# SCH_DMTBlinky_2025-11-07.net
KiCad netlist of a schematic drawn in EasyEDA
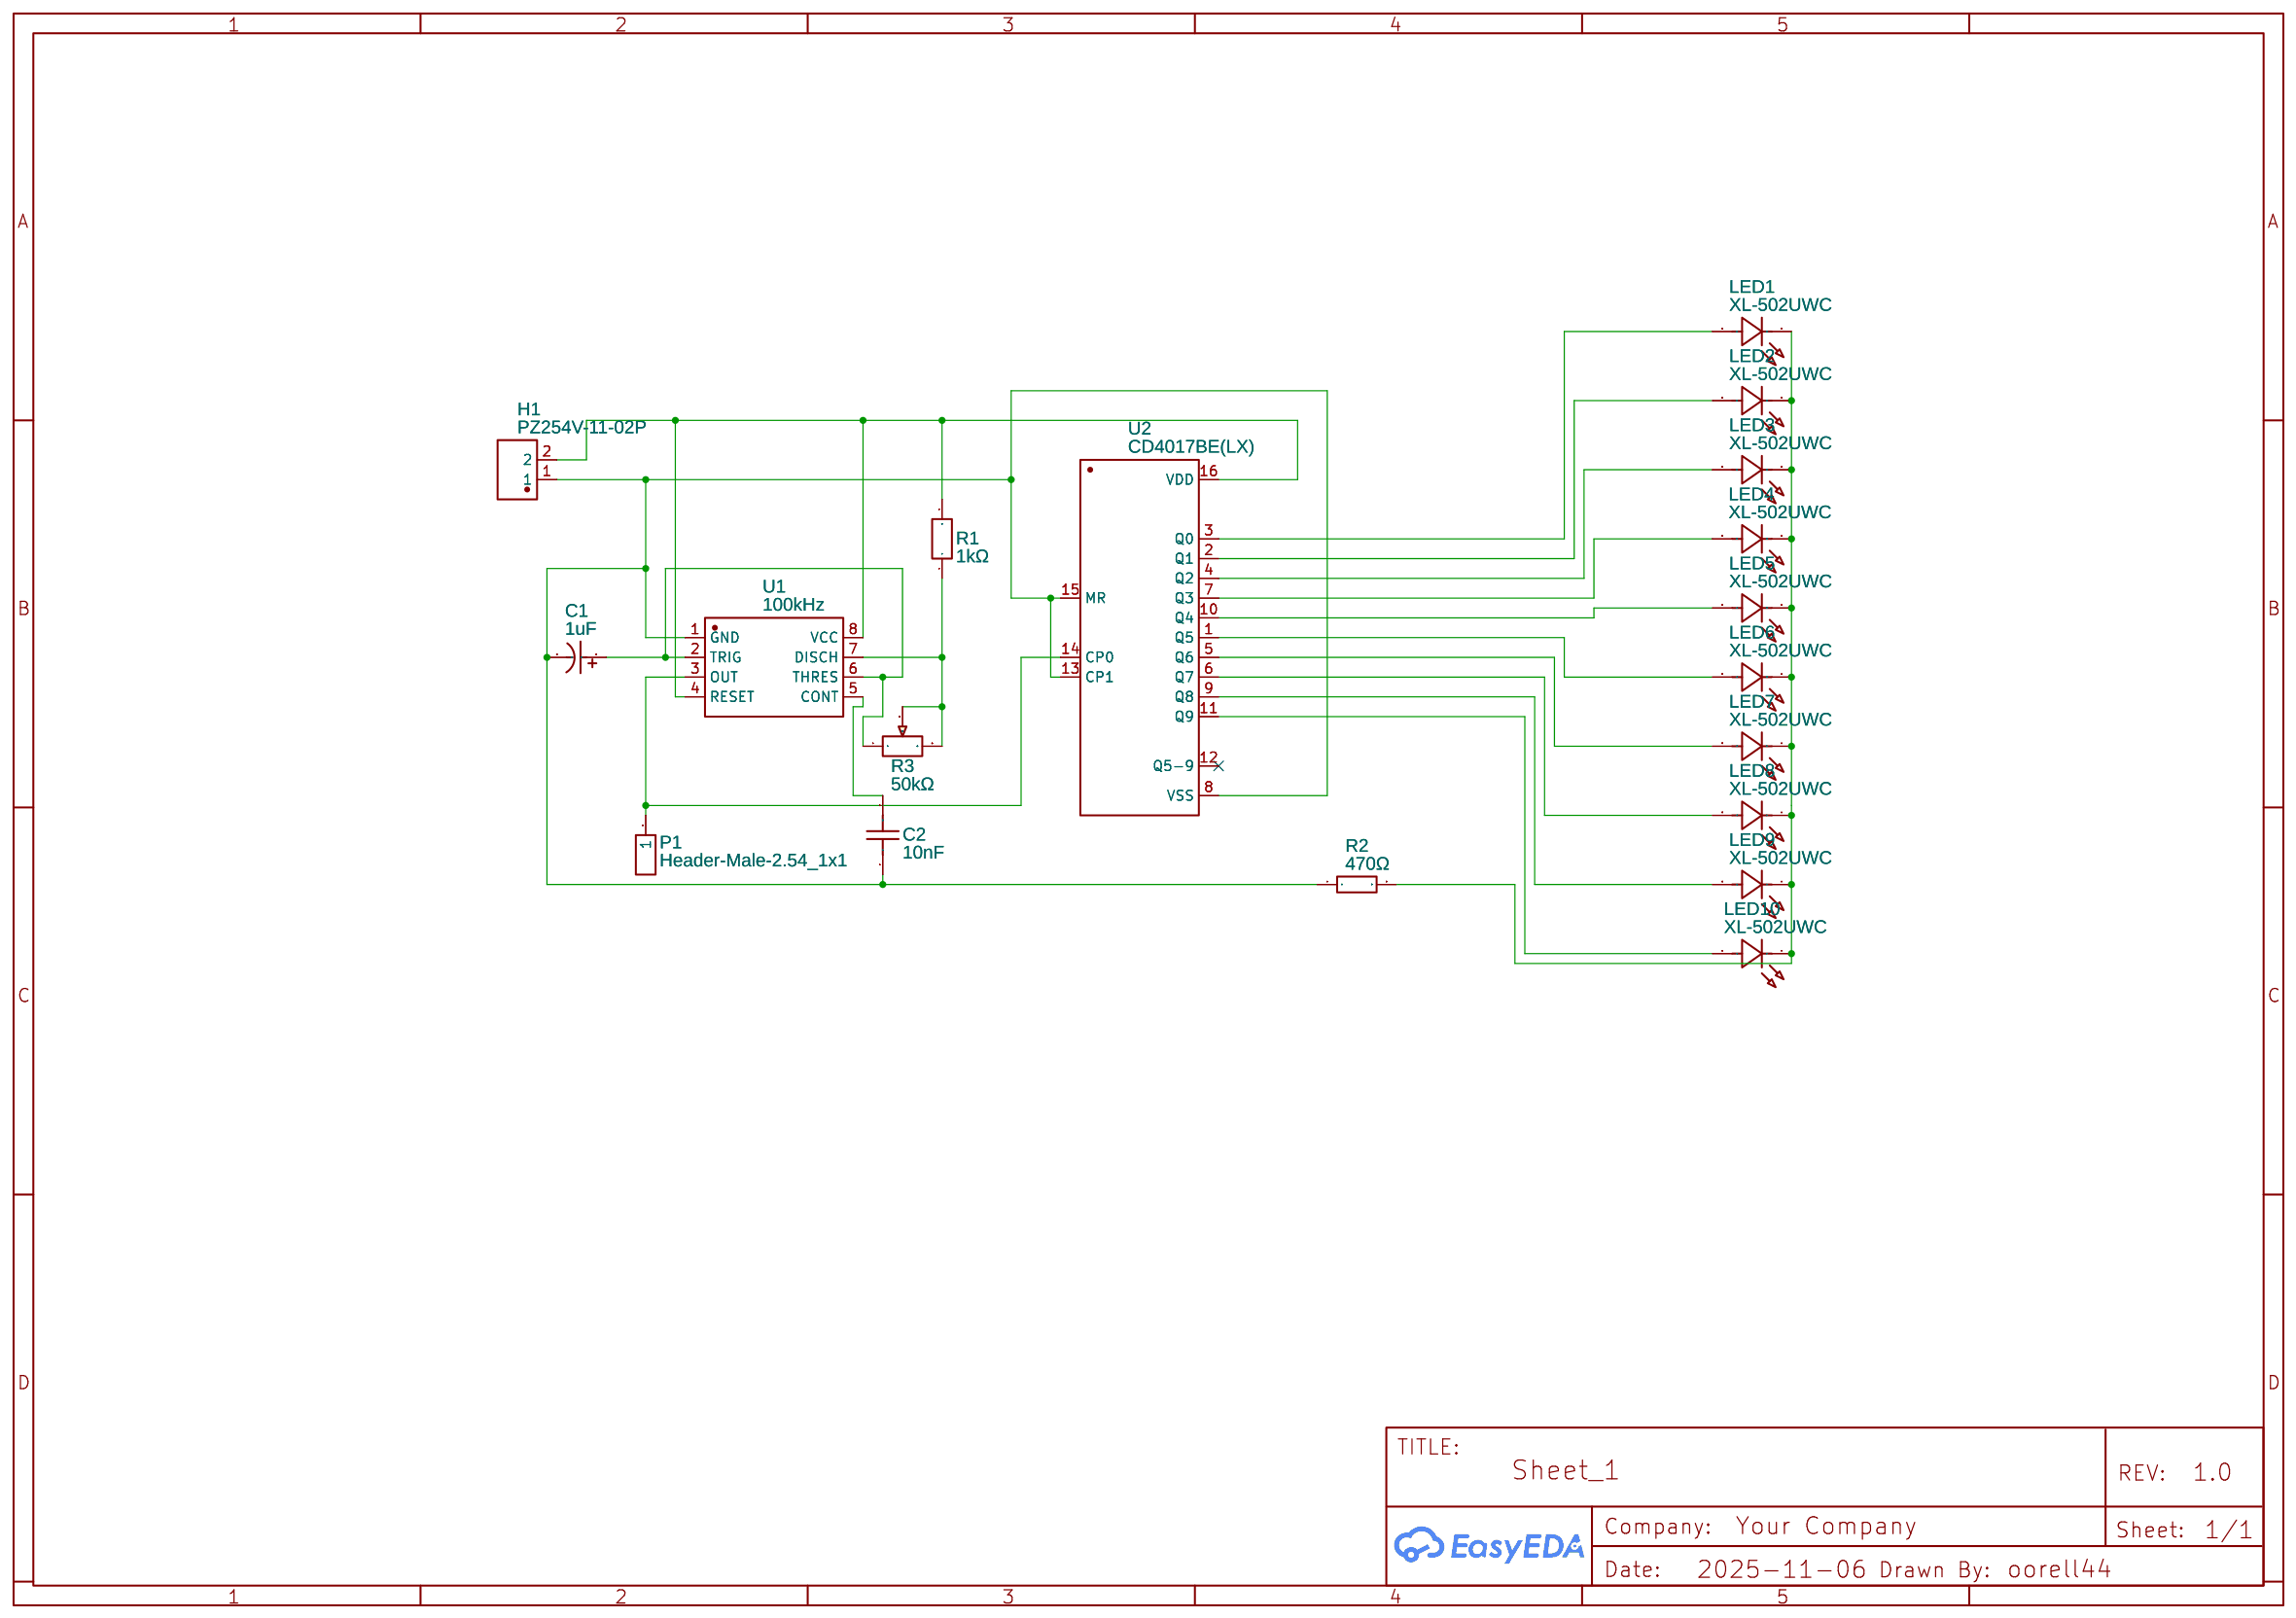
[diagram p0: schematic sheet]

(export (version "E")
  (design (tool "Eeschema 10.0.6"))
  (components
    (comp (ref "C1")
      (value "1uF")
      (fields (field (name "Manufacturer Part") "KF010M050C110A") (field (name "Manufacturer") "CapXon(丰宾)"))
      (libsource (lib "") (part "KF010M050C110A"))
    )
    (comp (ref "C2")
      (value "10nF")
      (fields (field (name "Manufacturer Part") "N09F1B103MN0B0S0N0") (field (name "Manufacturer") "STE(松田)"))
      (libsource (lib "") (part "N09F1B103MN0B0S0N0"))
    )
    (comp (ref "H1")
      (value "PZ254V-11-02P")
      (fields (field (name "Manufacturer") "XFCN(兴飞)"))
      (libsource (lib "") (part "PZ254V-11-02P"))
    )
    (comp (ref "LED1")
      (value "XL-502UWC")
      (fields (field (name "Manufacturer") "XINGLIGHT(成兴光)"))
      (libsource (lib "") (part "XL-502UWC"))
    )
    (comp (ref "LED2")
      (value "XL-502UWC")
      (fields (field (name "Manufacturer") "XINGLIGHT(成兴光)"))
      (libsource (lib "") (part "XL-502UWC"))
    )
    (comp (ref "LED3")
      (value "XL-502UWC")
      (fields (field (name "Manufacturer") "XINGLIGHT(成兴光)"))
      (libsource (lib "") (part "XL-502UWC"))
    )
    (comp (ref "LED4")
      (value "XL-502UWC")
      (fields (field (name "Manufacturer") "XINGLIGHT(成兴光)"))
      (libsource (lib "") (part "XL-502UWC"))
    )
    (comp (ref "LED5")
      (value "XL-502UWC")
      (fields (field (name "Manufacturer") "XINGLIGHT(成兴光)"))
      (libsource (lib "") (part "XL-502UWC"))
    )
    (comp (ref "LED6")
      (value "XL-502UWC")
      (fields (field (name "Manufacturer") "XINGLIGHT(成兴光)"))
      (libsource (lib "") (part "XL-502UWC"))
    )
    (comp (ref "LED7")
      (value "XL-502UWC")
      (fields (field (name "Manufacturer") "XINGLIGHT(成兴光)"))
      (libsource (lib "") (part "XL-502UWC"))
    )
    (comp (ref "LED8")
      (value "XL-502UWC")
      (fields (field (name "Manufacturer") "XINGLIGHT(成兴光)"))
      (libsource (lib "") (part "XL-502UWC"))
    )
    (comp (ref "LED9")
      (value "XL-502UWC")
      (fields (field (name "Manufacturer") "XINGLIGHT(成兴光)"))
      (libsource (lib "") (part "XL-502UWC"))
    )
    (comp (ref "LED10")
      (value "XL-502UWC")
      (fields (field (name "Manufacturer") "XINGLIGHT(成兴光)"))
      (libsource (lib "") (part "XL-502UWC"))
    )
    (comp (ref "P1")
      (value "Header-Male-2.54_1x1")
      (fields (field (name "Manufacturer Part") "2.54-1*1P针") (field (name "Manufacturer") "BOOMELE(博穆精密)"))
      (libsource (lib "") (part "Header-Male-2.54_1x1"))
    )
    (comp (ref "R1")
      (value "1kΩ")
      (fields (field (name "Manufacturer Part") "MF1/4W-1KΩ±1%T52") (field (name "Manufacturer") "华星机电"))
      (libsource (lib "") (part "MF1/4W-1KΩ±1%T52"))
    )
    (comp (ref "R2")
      (value "470Ω")
      (fields
        (field (name "Manufacturer Part") "MFR0W4F4700A50")
        (field (name "Manufacturer") "UNI-ROYAL(厚声)")
      )
      (libsource (lib "") (part "MFR0W4F4700A50"))
    )
    (comp (ref "R3")
      (value "50kΩ")
      (fields (field (name "Manufacturer Part") "3296X-1-503") (field (name "Manufacturer") "BOCHEN(博晨)"))
      (libsource (lib "") (part "3296X-1-503_C118912"))
    )
    (comp (ref "U1")
      (value "100kHz")
      (fields (field (name "Manufacturer Part") "NE555P") (field (name "Manufacturer") "TI(德州仪器)"))
      (libsource (lib "") (part "NE555P"))
    )
    (comp (ref "U2")
      (value "CD4017BE(LX)")
      (fields (field (name "Manufacturer") "LX(灵星芯微)"))
      (libsource (lib "") (part "CD4017BE(LX)"))
    )
  )
  (nets
    (net (code "1") (name "Net-(LED1-A)") (class "Default")
      (node (ref "LED1") (pin "2") (pinfunction "A_2") (pintype "unspecified"))
      (node (ref "U2") (pin "3") (pinfunction "Q0_3") (pintype "unspecified"))
    )
    (net (code "2") (name "Net-(LED1-K)") (class "Default")
      (node (ref "LED1") (pin "1") (pinfunction "K_1") (pintype "unspecified"))
      (node (ref "LED10") (pin "1") (pinfunction "K_1") (pintype "unspecified"))
      (node (ref "LED2") (pin "1") (pinfunction "K_1") (pintype "unspecified"))
      (node (ref "LED3") (pin "1") (pinfunction "K_1") (pintype "unspecified"))
      (node (ref "LED4") (pin "1") (pinfunction "K_1") (pintype "unspecified"))
      (node (ref "LED5") (pin "1") (pinfunction "K_1") (pintype "unspecified"))
      (node (ref "LED6") (pin "1") (pinfunction "K_1") (pintype "unspecified"))
      (node (ref "LED7") (pin "1") (pinfunction "K_1") (pintype "unspecified"))
      (node (ref "LED8") (pin "1") (pinfunction "K_1") (pintype "unspecified"))
      (node (ref "LED9") (pin "1") (pinfunction "K_1") (pintype "unspecified"))
      (node (ref "R2") (pin "2") (pinfunction "2_2") (pintype "input"))
    )
    (net (code "3") (name "Net-(LED2-A)") (class "Default")
      (node (ref "LED2") (pin "2") (pinfunction "A_2") (pintype "unspecified"))
      (node (ref "U2") (pin "2") (pinfunction "Q1_2") (pintype "unspecified"))
    )
    (net (code "4") (name "Net-(LED3-A)") (class "Default")
      (node (ref "LED3") (pin "2") (pinfunction "A_2") (pintype "unspecified"))
      (node (ref "U2") (pin "4") (pinfunction "Q2_4") (pintype "unspecified"))
    )
    (net (code "5") (name "Net-(LED4-A)") (class "Default")
      (node (ref "LED4") (pin "2") (pinfunction "A_2") (pintype "unspecified"))
      (node (ref "U2") (pin "7") (pinfunction "Q3_7") (pintype "unspecified"))
    )
    (net (code "6") (name "Net-(LED5-A)") (class "Default")
      (node (ref "LED5") (pin "2") (pinfunction "A_2") (pintype "unspecified"))
      (node (ref "U2") (pin "10") (pinfunction "Q4_10") (pintype "unspecified"))
    )
    (net (code "7") (name "Net-(LED6-A)") (class "Default")
      (node (ref "LED6") (pin "2") (pinfunction "A_2") (pintype "unspecified"))
      (node (ref "U2") (pin "1") (pinfunction "Q5_1") (pintype "unspecified"))
    )
    (net (code "8") (name "Net-(LED7-A)") (class "Default")
      (node (ref "LED7") (pin "2") (pinfunction "A_2") (pintype "unspecified"))
      (node (ref "U2") (pin "5") (pinfunction "Q6_5") (pintype "unspecified"))
    )
    (net (code "9") (name "Net-(LED8-A)") (class "Default")
      (node (ref "LED8") (pin "2") (pinfunction "A_2") (pintype "unspecified"))
      (node (ref "U2") (pin "6") (pinfunction "Q7_6") (pintype "unspecified"))
    )
    (net (code "10") (name "Net-(LED9-A)") (class "Default")
      (node (ref "LED9") (pin "2") (pinfunction "A_2") (pintype "unspecified"))
      (node (ref "U2") (pin "9") (pinfunction "Q8_9") (pintype "unspecified"))
    )
    (net (code "11") (name "Net-(LED10-A)") (class "Default")
      (node (ref "LED10") (pin "2") (pinfunction "A_2") (pintype "unspecified"))
      (node (ref "U2") (pin "11") (pinfunction "Q9_11") (pintype "unspecified"))
    )
    (net (code "12") (name "Net-(U1-CONT)") (class "Default")
      (node (ref "C2") (pin "2") (pinfunction "2_2") (pintype "unspecified"))
      (node (ref "U1") (pin "5") (pinfunction "CONT_5") (pintype "unspecified"))
    )
    (net (code "13") (name "Net-(U1-DISCH)") (class "Default")
      (node (ref "R1") (pin "1") (pinfunction "1_1") (pintype "unspecified"))
      (node (ref "R3") (pin "2") (pinfunction "2_2") (pintype "input"))
      (node (ref "R3") (pin "3") (pinfunction "3_3") (pintype "input"))
      (node (ref "U1") (pin "7") (pinfunction "DISCH_7") (pintype "unspecified"))
    )
    (net (code "14") (name "Net-(U1-GND)") (class "Default")
      (node (ref "C1") (pin "2") (pinfunction "2_2") (pintype "input"))
      (node (ref "C2") (pin "1") (pinfunction "1_1") (pintype "unspecified"))
      (node (ref "H1") (pin "1") (pinfunction "1_1") (pintype "unspecified"))
      (node (ref "R2") (pin "1") (pinfunction "1_1") (pintype "input"))
      (node (ref "U1") (pin "1") (pinfunction "GND_1") (pintype "unspecified"))
      (node (ref "U2") (pin "13") (pinfunction "CP1_13") (pintype "unspecified"))
      (node (ref "U2") (pin "15") (pinfunction "MR_15") (pintype "unspecified"))
      (node (ref "U2") (pin "8") (pinfunction "VSS_8") (pintype "unspecified"))
    )
    (net (code "15") (name "Net-(U1-OUT)") (class "Default")
      (node (ref "P1") (pin "1") (pinfunction "1_1") (pintype "input"))
      (node (ref "U1") (pin "3") (pinfunction "OUT_3") (pintype "unspecified"))
      (node (ref "U2") (pin "14") (pinfunction "CP0_14") (pintype "unspecified"))
    )
    (net (code "16") (name "Net-(U1-RESET)") (class "Default")
      (node (ref "H1") (pin "2") (pinfunction "2_2") (pintype "unspecified"))
      (node (ref "R1") (pin "2") (pinfunction "2_2") (pintype "unspecified"))
      (node (ref "U1") (pin "4") (pinfunction "RESET_4") (pintype "unspecified"))
      (node (ref "U1") (pin "8") (pinfunction "VCC_8") (pintype "unspecified"))
      (node (ref "U2") (pin "16") (pinfunction "VDD_16") (pintype "unspecified"))
    )
    (net (code "17") (name "Net-(U1-THRES)") (class "Default")
      (node (ref "C1") (pin "1") (pinfunction "1_1") (pintype "input"))
      (node (ref "R3") (pin "1") (pinfunction "1_1") (pintype "input"))
      (node (ref "U1") (pin "2") (pinfunction "TRIG_2") (pintype "unspecified"))
      (node (ref "U1") (pin "6") (pinfunction "THRES_6") (pintype "unspecified"))
    )
    (net (code "18") (name "unconnected-(U2-Q5-9-Pad12)") (class "Default")
      (node (ref "U2") (pin "12") (pinfunction "Q5-9_12") (pintype "unspecified+no_connect"))
    )
  )
)
